# Net.net
KiCad netlist of a schematic drawn in Altium Designer
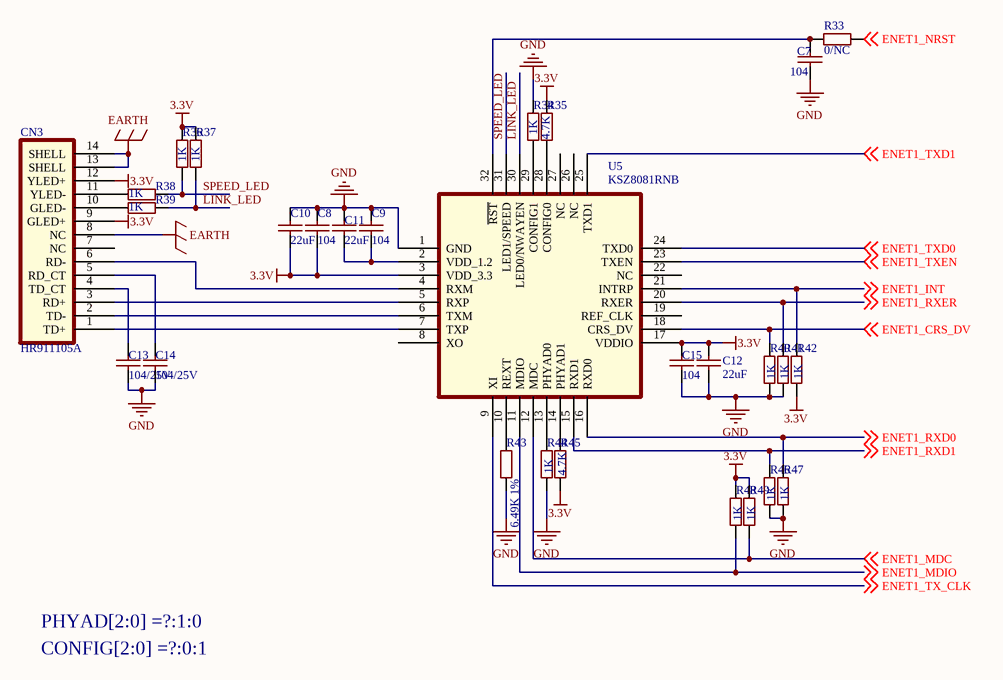
[diagram p0: Net.SchDoc]

(export (version "E")
  (design (tool "Eeschema 10.0.6"))
  (components
    (comp (ref "C7")
      (value "104")
      (footprint "0805SMD_Cap")
      (description "贴片电容")
      (libsource (lib "ST_GND_Sch") (part "SMD_Cap"))
    )
    (comp (ref "C8")
      (value "104")
      (footprint "0805SMD_Cap")
      (description "贴片电容")
      (libsource (lib "ST_GND_Sch") (part "SMD_Cap"))
    )
    (comp (ref "C9")
      (value "104")
      (footprint "0805SMD_Cap")
      (description "贴片电容")
      (libsource (lib "ST_GND_Sch") (part "SMD_Cap"))
    )
    (comp (ref "C10")
      (value "22uF")
      (footprint "0805SMD_Cap")
      (description "贴片电容")
      (libsource (lib "ST_GND_Sch") (part "SMD_Cap"))
    )
    (comp (ref "C11")
      (value "22uF")
      (footprint "0805SMD_Cap")
      (description "贴片电容")
      (libsource (lib "ST_GND_Sch") (part "SMD_Cap"))
    )
    (comp (ref "C12")
      (value "22uF")
      (footprint "0805SMD_Cap")
      (description "贴片电容")
      (libsource (lib "ST_GND_Sch") (part "SMD_Cap"))
    )
    (comp (ref "C13")
      (value "104/25V")
      (footprint "0805SMD_Cap")
      (description "贴片电容")
      (libsource (lib "ST_GND_Sch") (part "SMD_Cap"))
    )
    (comp (ref "C14")
      (value "104/25V")
      (footprint "0805SMD_Cap")
      (description "贴片电容")
      (libsource (lib "ST_GND_Sch") (part "SMD_Cap"))
    )
    (comp (ref "C15")
      (value "104")
      (footprint "0805SMD_Cap")
      (description "贴片电容")
      (libsource (lib "ST_GND_Sch") (part "SMD_Cap"))
    )
    (comp (ref "CN3")
      (value "HR911105A")
      (footprint "RJ-45A12")
      (libsource (lib "ST_GND_Sch") (part "HR911105A"))
    )
    (comp (ref "R33")
      (value "0/NC")
      (footprint "0805_SMD_R")
      (description "贴片电阻")
      (libsource (lib "") (part "SMD_0805_2"))
    )
    (comp (ref "R34")
      (value "1K")
      (footprint "0805_SMD_R")
      (description "贴片电阻")
      (libsource (lib "ST_GND_Sch") (part "SMD_0805"))
    )
    (comp (ref "R35")
      (value "4.7K")
      (footprint "0805_SMD_R")
      (description "贴片电阻")
      (libsource (lib "ST_GND_Sch") (part "SMD_0805"))
    )
    (comp (ref "R36")
      (value "1K")
      (footprint "0805_SMD_R")
      (description "贴片电阻")
      (libsource (lib "ST_GND_Sch") (part "SMD_0805"))
    )
    (comp (ref "R37")
      (value "1K")
      (footprint "0805_SMD_R")
      (description "贴片电阻")
      (libsource (lib "ST_GND_Sch") (part "SMD_0805"))
    )
    (comp (ref "R38")
      (value "1K")
      (footprint "0805_SMD_R")
      (description "贴片电阻")
      (libsource (lib "") (part "SMD_0805_1"))
    )
    (comp (ref "R39")
      (value "1K")
      (footprint "0805_SMD_R")
      (description "贴片电阻")
      (libsource (lib "") (part "SMD_0805_1"))
    )
    (comp (ref "R40")
      (value "1K")
      (footprint "0805_SMD_R")
      (description "贴片电阻")
      (libsource (lib "ST_GND_Sch") (part "SMD_0805"))
    )
    (comp (ref "R41")
      (value "1K")
      (footprint "0805_SMD_R")
      (description "贴片电阻")
      (libsource (lib "ST_GND_Sch") (part "SMD_0805"))
    )
    (comp (ref "R42")
      (value "1K")
      (footprint "0805_SMD_R")
      (description "贴片电阻")
      (libsource (lib "") (part "SMD_0805_3"))
    )
    (comp (ref "R43")
      (value "6.49K 1%")
      (footprint "0805_SMD_R")
      (description "贴片电阻")
      (libsource (lib "ST_GND_Sch") (part "SMD_0805"))
    )
    (comp (ref "R44")
      (value "1K")
      (footprint "0805_SMD_R")
      (description "贴片电阻")
      (libsource (lib "ST_GND_Sch") (part "SMD_0805"))
    )
    (comp (ref "R45")
      (value "4.7K")
      (footprint "0805_SMD_R")
      (description "贴片电阻")
      (libsource (lib "") (part "SMD_0805_3"))
    )
    (comp (ref "R46")
      (value "1K")
      (footprint "0805_SMD_R")
      (description "贴片电阻")
      (libsource (lib "ST_GND_Sch") (part "SMD_0805"))
    )
    (comp (ref "R47")
      (value "1K")
      (footprint "0805_SMD_R")
      (description "贴片电阻")
      (libsource (lib "ST_GND_Sch") (part "SMD_0805"))
    )
    (comp (ref "R48")
      (value "1K")
      (footprint "0805_SMD_R")
      (description "贴片电阻")
      (libsource (lib "ST_GND_Sch") (part "SMD_0805"))
    )
    (comp (ref "R49")
      (value "1K")
      (footprint "0805_SMD_R")
      (description "贴片电阻")
      (libsource (lib "ST_GND_Sch") (part "SMD_0805"))
    )
    (comp (ref "U5")
      (value "KSZ8081RNB")
      (footprint "LC-QFN-32_5x5x05P")
      (libsource (lib "ST_GND_Sch") (part "KSZ8081RNB"))
    )
  )
  (nets
    (net (code "1") (name "/LINK_LED") (class "Default")
      (node (ref "R37") (pin "1") (pinfunction "1_1") (pintype "passive"))
      (node (ref "R39") (pin "2") (pinfunction "2_2") (pintype "passive"))
      (node (ref "U5") (pin "30") (pinfunction "LED0/NWAYEN_30") (pintype "passive"))
    )
    (net (code "2") (name "/SPEED_LED") (class "Default")
      (node (ref "R36") (pin "1") (pinfunction "1_1") (pintype "passive"))
      (node (ref "R38") (pin "2") (pinfunction "2_2") (pintype "passive"))
      (node (ref "U5") (pin "31") (pinfunction "LED1/SPEED_31") (pintype "passive"))
    )
    (net (code "3") (name "3.3V") (class "Default")
      (node (ref "C10") (pin "1") (pintype "passive"))
      (node (ref "C12") (pin "1") (pintype "passive"))
      (node (ref "C15") (pin "2") (pintype "passive"))
      (node (ref "C8") (pin "2") (pintype "passive"))
      (node (ref "CN3") (pin "12") (pinfunction "YLED+_12") (pintype "passive"))
      (node (ref "CN3") (pin "9") (pinfunction "GLED+_9") (pintype "passive"))
      (node (ref "R35") (pin "2") (pinfunction "2_2") (pintype "passive"))
      (node (ref "R36") (pin "2") (pinfunction "2_2") (pintype "passive"))
      (node (ref "R37") (pin "2") (pinfunction "2_2") (pintype "passive"))
      (node (ref "R42") (pin "2") (pinfunction "2_2") (pintype "passive"))
      (node (ref "R45") (pin "2") (pinfunction "2_2") (pintype "passive"))
      (node (ref "R48") (pin "2") (pinfunction "2_2") (pintype "passive"))
      (node (ref "R49") (pin "2") (pinfunction "2_2") (pintype "passive"))
      (node (ref "U5") (pin "17") (pinfunction "VDDIO_17") (pintype "passive"))
      (node (ref "U5") (pin "3") (pinfunction "VDD_3.3_3") (pintype "power_in"))
    )
    (net (code "4") (name "EARTH") (class "Default")
      (node (ref "CN3") (pin "13") (pinfunction "SHELL_13") (pintype "passive"))
      (node (ref "CN3") (pin "14") (pinfunction "SHELL_14") (pintype "passive"))
      (node (ref "CN3") (pin "8") (pinfunction "NC_8") (pintype "passive"))
    )
    (net (code "5") (name "ENET1_CRS_DV") (class "Default")
      (node (ref "R40") (pin "2") (pinfunction "2_2") (pintype "passive"))
      (node (ref "U5") (pin "18") (pinfunction "CRS_DV_18") (pintype "passive"))
    )
    (net (code "6") (name "ENET1_INT") (class "Default")
      (node (ref "R42") (pin "1") (pinfunction "1_1") (pintype "passive"))
      (node (ref "U5") (pin "21") (pinfunction "INTRP_21") (pintype "passive"))
    )
    (net (code "7") (name "ENET1_MDC") (class "Default")
      (node (ref "R49") (pin "1") (pinfunction "1_1") (pintype "passive"))
      (node (ref "U5") (pin "12") (pinfunction "MDC_12") (pintype "passive"))
    )
    (net (code "8") (name "ENET1_MDIO") (class "Default")
      (node (ref "R48") (pin "1") (pinfunction "1_1") (pintype "passive"))
      (node (ref "U5") (pin "11") (pinfunction "MDIO_11") (pintype "passive"))
    )
    (net (code "9") (name "ENET1_NRST") (class "Default")
      (node (ref "R33") (pin "1") (pinfunction "1_1") (pintype "passive"))
    )
    (net (code "10") (name "ENET1_RXD0") (class "Default")
      (node (ref "R47") (pin "2") (pinfunction "2_2") (pintype "passive"))
      (node (ref "U5") (pin "16") (pinfunction "RXD0_16") (pintype "passive"))
    )
    (net (code "11") (name "ENET1_RXD1") (class "Default")
      (node (ref "R46") (pin "2") (pinfunction "2_2") (pintype "passive"))
      (node (ref "U5") (pin "15") (pinfunction "RXD1_15") (pintype "passive"))
    )
    (net (code "12") (name "ENET1_RXER") (class "Default")
      (node (ref "R41") (pin "2") (pinfunction "2_2") (pintype "passive"))
      (node (ref "U5") (pin "20") (pinfunction "RXER_20") (pintype "passive"))
    )
    (net (code "13") (name "ENET1_TXD0") (class "Default")
      (node (ref "U5") (pin "24") (pinfunction "TXD0_24") (pintype "passive"))
    )
    (net (code "14") (name "ENET1_TXD1") (class "Default")
      (node (ref "U5") (pin "25") (pinfunction "TXD1_25") (pintype "passive"))
    )
    (net (code "15") (name "ENET1_TXEN") (class "Default")
      (node (ref "U5") (pin "23") (pinfunction "TXEN_23") (pintype "passive"))
    )
    (net (code "16") (name "ENET1_TX_CLK") (class "Default")
      (node (ref "U5") (pin "9") (pinfunction "XI_9") (pintype "passive"))
    )
    (net (code "17") (name "GND") (class "Default")
      (node (ref "C10") (pin "2") (pintype "passive"))
      (node (ref "C11") (pin "2") (pintype "passive"))
      (node (ref "C12") (pin "2") (pintype "passive"))
      (node (ref "C13") (pin "1") (pintype "passive"))
      (node (ref "C14") (pin "1") (pintype "passive"))
      (node (ref "C15") (pin "1") (pintype "passive"))
      (node (ref "C7") (pin "1") (pintype "passive"))
      (node (ref "C8") (pin "1") (pintype "passive"))
      (node (ref "C9") (pin "1") (pintype "passive"))
      (node (ref "R34") (pin "2") (pinfunction "2_2") (pintype "passive"))
      (node (ref "R40") (pin "1") (pinfunction "1_1") (pintype "passive"))
      (node (ref "R41") (pin "1") (pinfunction "1_1") (pintype "passive"))
      (node (ref "R43") (pin "1") (pinfunction "1_1") (pintype "passive"))
      (node (ref "R44") (pin "1") (pinfunction "1_1") (pintype "passive"))
      (node (ref "R46") (pin "1") (pinfunction "1_1") (pintype "passive"))
      (node (ref "R47") (pin "1") (pinfunction "1_1") (pintype "passive"))
      (node (ref "U5") (pin "1") (pinfunction "GND_1") (pintype "passive"))
    )
    (net (code "18") (name "Net-(CN3-GLED-)") (class "Default")
      (node (ref "CN3") (pin "10") (pinfunction "GLED-_10") (pintype "passive"))
      (node (ref "R39") (pin "1") (pinfunction "1_1") (pintype "passive"))
    )
    (net (code "19") (name "Net-(CN3-RD+)") (class "Default")
      (node (ref "CN3") (pin "3") (pinfunction "RD+_3") (pintype "passive"))
      (node (ref "U5") (pin "5") (pinfunction "RXP_5") (pintype "passive"))
    )
    (net (code "20") (name "Net-(CN3-RD-)") (class "Default")
      (node (ref "CN3") (pin "6") (pinfunction "RD-_6") (pintype "passive"))
      (node (ref "U5") (pin "4") (pinfunction "RXM_4") (pintype "passive"))
    )
    (net (code "21") (name "Net-(CN3-RD_CT)") (class "Default")
      (node (ref "C14") (pin "2") (pintype "passive"))
      (node (ref "CN3") (pin "5") (pinfunction "RD_CT_5") (pintype "passive"))
    )
    (net (code "22") (name "Net-(CN3-TD+)") (class "Default")
      (node (ref "CN3") (pin "1") (pinfunction "TD+_1") (pintype "passive"))
      (node (ref "U5") (pin "7") (pinfunction "TXP_7") (pintype "passive"))
    )
    (net (code "23") (name "Net-(CN3-TD-)") (class "Default")
      (node (ref "CN3") (pin "2") (pinfunction "TD-_2") (pintype "passive"))
      (node (ref "U5") (pin "6") (pinfunction "TXM_6") (pintype "passive"))
    )
    (net (code "24") (name "Net-(CN3-TD_CT)") (class "Default")
      (node (ref "C13") (pin "2") (pintype "passive"))
      (node (ref "CN3") (pin "4") (pinfunction "TD_CT_4") (pintype "passive"))
    )
    (net (code "25") (name "Net-(CN3-YLED-)") (class "Default")
      (node (ref "CN3") (pin "11") (pinfunction "YLED-_11") (pintype "passive"))
      (node (ref "R38") (pin "1") (pinfunction "1_1") (pintype "passive"))
    )
    (net (code "26") (name "Net-(U5-CONFIG0)") (class "Default")
      (node (ref "R35") (pin "1") (pinfunction "1_1") (pintype "passive"))
      (node (ref "U5") (pin "28") (pinfunction "CONFIG0_28") (pintype "passive"))
    )
    (net (code "27") (name "Net-(U5-CONFIG1)") (class "Default")
      (node (ref "R34") (pin "1") (pinfunction "1_1") (pintype "passive"))
      (node (ref "U5") (pin "29") (pinfunction "CONFIG1_29") (pintype "passive"))
    )
    (net (code "28") (name "Net-(U5-PHYAD0)") (class "Default")
      (node (ref "R44") (pin "2") (pinfunction "2_2") (pintype "passive"))
      (node (ref "U5") (pin "13") (pinfunction "PHYAD0_13") (pintype "passive"))
    )
    (net (code "29") (name "Net-(U5-PHYAD1)") (class "Default")
      (node (ref "R45") (pin "1") (pinfunction "1_1") (pintype "passive"))
      (node (ref "U5") (pin "14") (pinfunction "PHYAD1_14") (pintype "passive"))
    )
    (net (code "30") (name "Net-(U5-REXT)") (class "Default")
      (node (ref "R43") (pin "2") (pinfunction "2_2") (pintype "passive"))
      (node (ref "U5") (pin "10") (pinfunction "REXT_10") (pintype "passive"))
    )
    (net (code "31") (name "Net-(U5-VDD_1.2)") (class "Default")
      (node (ref "C11") (pin "1") (pintype "passive"))
      (node (ref "C9") (pin "2") (pintype "passive"))
      (node (ref "U5") (pin "2") (pinfunction "VDD_1.2_2") (pintype "passive"))
    )
    (net (code "32") (name "Net-(U5-~{RST})") (class "Default")
      (node (ref "C7") (pin "2") (pintype "passive"))
      (node (ref "R33") (pin "2") (pinfunction "2_2") (pintype "passive"))
      (node (ref "U5") (pin "32") (pinfunction "~{RST}_32") (pintype "passive"))
    )
    (net (code "33") (name "unconnected-(CN3-NC-Pad7)") (class "Default")
      (node (ref "CN3") (pin "7") (pinfunction "NC_7") (pintype "passive"))
    )
    (net (code "34") (name "unconnected-(U5-NC-Pad22)") (class "Default")
      (node (ref "U5") (pin "22") (pinfunction "NC_22") (pintype "passive"))
    )
    (net (code "35") (name "unconnected-(U5-NC-Pad26)") (class "Default")
      (node (ref "U5") (pin "26") (pinfunction "NC_26") (pintype "passive"))
    )
    (net (code "36") (name "unconnected-(U5-NC-Pad27)") (class "Default")
      (node (ref "U5") (pin "27") (pinfunction "NC_27") (pintype "passive"))
    )
    (net (code "37") (name "unconnected-(U5-REF_CLK-Pad19)") (class "Default")
      (node (ref "U5") (pin "19") (pinfunction "REF_CLK_19") (pintype "passive"))
    )
    (net (code "38") (name "unconnected-(U5-XO-Pad8)") (class "Default")
      (node (ref "U5") (pin "8") (pinfunction "XO_8") (pintype "passive"))
    )
  )
)
